# board_kelengkeng_v2.net
KiCad netlist of a schematic drawn in EAGLE
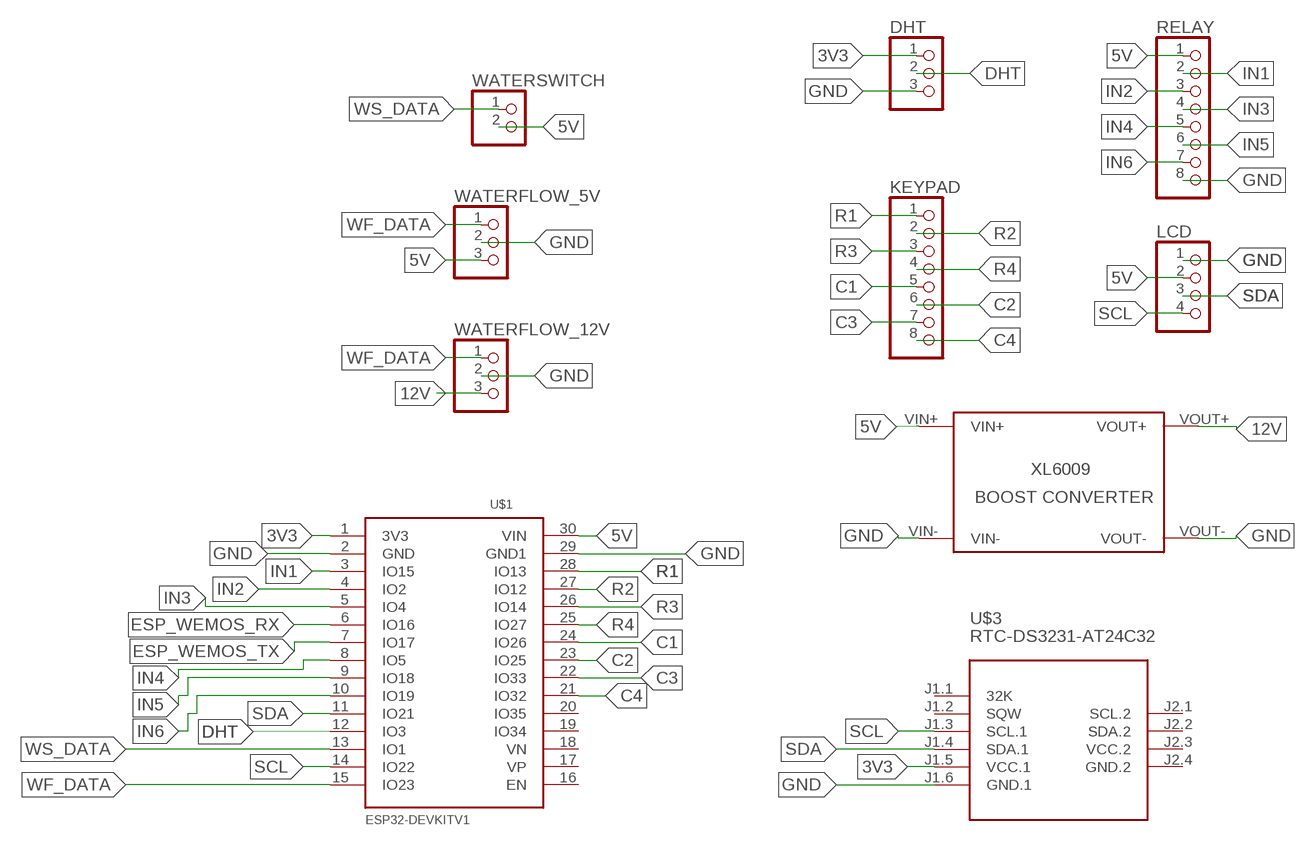
[diagram p0: schematic, sheet 1]

(export (version "E")
  (design (tool "Eeschema 10.0.6"))
  (components
    (comp (ref "DHT")
      (value "PINHD-1X3")
      (footprint "eagle-import:1X03")
      (libsource (lib "eagle-import") (part "PINHD-1X3"))
    )
    (comp (ref "KEYPAD")
      (value "PINHD-1X8")
      (footprint "eagle-import:1X08")
      (libsource (lib "eagle-import") (part "PINHD-1X8"))
    )
    (comp (ref "LCD")
      (value "PINHD-1X4")
      (footprint "eagle-import:1X04")
      (libsource (lib "eagle-import") (part "PINHD-1X4"))
    )
    (comp (ref "RELAY")
      (value "PINHD-1X8")
      (footprint "eagle-import:1X08")
      (libsource (lib "eagle-import") (part "PINHD-1X8"))
    )
    (comp (ref "U$1")
      (value "ESP32DEVKITV1")
      (footprint "eagle-import:ESP32-DEVKITV1")
      (libsource (lib "eagle-import") (part "ESP32DEVKITV1"))
    )
    (comp (ref "U$2")
      (value "XL6009")
      (footprint "eagle-import:XL6009")
      (libsource (lib "eagle-import") (part "XL6009"))
    )
    (comp (ref "U$3")
      (value "RTC-DS3231-AT24C32")
      (footprint "eagle-import:RTC-DS3231-AT24C32")
      (libsource (lib "eagle-import") (part "RTC-DS3231-AT24C32"))
    )
    (comp (ref "WATERFLOW_5V")
      (value "PINHD-1X3")
      (footprint "eagle-import:1X03")
      (libsource (lib "eagle-import") (part "PINHD-1X3"))
    )
    (comp (ref "WATERFLOW_12V")
      (value "PINHD-1X3")
      (footprint "eagle-import:1X03")
      (libsource (lib "eagle-import") (part "PINHD-1X3"))
    )
    (comp (ref "WATERSWITCH")
      (value "PINHD-1X2")
      (footprint "eagle-import:1X02")
      (libsource (lib "eagle-import") (part "PINHD-1X2"))
    )
  )
  (nets
    (net (code "1") (name "/GND.2") (class "Default")
      (node (ref "U$3") (pin "J2.4") (pinfunction "GND.2_J2.4") (pintype "power_in"))
    )
    (net (code "2") (name "/VCC.2") (class "Default")
      (node (ref "U$3") (pin "J2.3") (pinfunction "VCC.2_J2.3") (pintype "power_in"))
    )
    (net (code "3") (name "3V3") (class "Default")
      (node (ref "DHT") (pin "1") (pinfunction "1_1") (pintype "passive"))
      (node (ref "U$1") (pin "1") (pinfunction "3V3_1") (pintype "bidirectional"))
      (node (ref "U$3") (pin "J1.5") (pinfunction "VCC.1_J1.5") (pintype "power_in"))
    )
    (net (code "4") (name "5V") (class "Default")
      (node (ref "LCD") (pin "2") (pinfunction "2_2") (pintype "passive"))
      (node (ref "RELAY") (pin "1") (pinfunction "1_1") (pintype "passive"))
      (node (ref "U$1") (pin "30") (pinfunction "VIN_30") (pintype "bidirectional"))
      (node (ref "U$2") (pin "VIN+") (pinfunction "VIN+_VIN+") (pintype "bidirectional"))
      (node (ref "WATERFLOW_5V") (pin "3") (pinfunction "3_3") (pintype "passive"))
      (node (ref "WATERSWITCH") (pin "2") (pinfunction "2_2") (pintype "passive"))
    )
    (net (code "5") (name "12V") (class "Default")
      (node (ref "U$2") (pin "VOUT+") (pinfunction "VOUT+_VOUT+") (pintype "bidirectional"))
      (node (ref "WATERFLOW_12V") (pin "3") (pinfunction "3_3") (pintype "passive"))
    )
    (net (code "6") (name "C1") (class "Default")
      (node (ref "KEYPAD") (pin "5") (pinfunction "5_5") (pintype "passive"))
      (node (ref "U$1") (pin "24") (pinfunction "IO26_24") (pintype "bidirectional"))
    )
    (net (code "7") (name "C2") (class "Default")
      (node (ref "KEYPAD") (pin "6") (pinfunction "6_6") (pintype "passive"))
      (node (ref "U$1") (pin "23") (pinfunction "IO25_23") (pintype "bidirectional"))
    )
    (net (code "8") (name "C3") (class "Default")
      (node (ref "KEYPAD") (pin "7") (pinfunction "7_7") (pintype "passive"))
      (node (ref "U$1") (pin "22") (pinfunction "IO33_22") (pintype "bidirectional"))
    )
    (net (code "9") (name "C4") (class "Default")
      (node (ref "KEYPAD") (pin "8") (pinfunction "8_8") (pintype "passive"))
      (node (ref "U$1") (pin "21") (pinfunction "IO32_21") (pintype "bidirectional"))
    )
    (net (code "10") (name "DHT") (class "Default")
      (node (ref "DHT") (pin "2") (pinfunction "2_2") (pintype "passive"))
      (node (ref "U$1") (pin "12") (pinfunction "IO3_12") (pintype "bidirectional"))
    )
    (net (code "11") (name "ESP_WEMOS_RX") (class "Default")
      (node (ref "U$1") (pin "6") (pinfunction "IO16_6") (pintype "bidirectional"))
    )
    (net (code "12") (name "ESP_WEMOS_TX") (class "Default")
      (node (ref "U$1") (pin "7") (pinfunction "IO17_7") (pintype "bidirectional"))
    )
    (net (code "13") (name "GND") (class "Default")
      (node (ref "DHT") (pin "3") (pinfunction "3_3") (pintype "passive"))
      (node (ref "LCD") (pin "1") (pinfunction "1_1") (pintype "passive"))
      (node (ref "RELAY") (pin "8") (pinfunction "8_8") (pintype "passive"))
      (node (ref "U$1") (pin "2") (pinfunction "GND_2") (pintype "bidirectional"))
      (node (ref "U$1") (pin "29") (pinfunction "GND1_29") (pintype "bidirectional"))
      (node (ref "U$2") (pin "VIN-") (pinfunction "VIN-_VIN-") (pintype "bidirectional"))
      (node (ref "U$2") (pin "VOUT-") (pinfunction "VOUT-_VOUT-") (pintype "bidirectional"))
      (node (ref "U$3") (pin "J1.6") (pinfunction "GND.1_J1.6") (pintype "power_in"))
      (node (ref "WATERFLOW_12V") (pin "2") (pinfunction "2_2") (pintype "passive"))
      (node (ref "WATERFLOW_5V") (pin "2") (pinfunction "2_2") (pintype "passive"))
    )
    (net (code "14") (name "IN1") (class "Default")
      (node (ref "RELAY") (pin "2") (pinfunction "2_2") (pintype "passive"))
      (node (ref "U$1") (pin "3") (pinfunction "IO15_3") (pintype "bidirectional"))
    )
    (net (code "15") (name "IN2") (class "Default")
      (node (ref "RELAY") (pin "3") (pinfunction "3_3") (pintype "passive"))
      (node (ref "U$1") (pin "4") (pinfunction "IO2_4") (pintype "bidirectional"))
    )
    (net (code "16") (name "IN3") (class "Default")
      (node (ref "RELAY") (pin "4") (pinfunction "4_4") (pintype "passive"))
      (node (ref "U$1") (pin "5") (pinfunction "IO4_5") (pintype "bidirectional"))
    )
    (net (code "17") (name "IN4") (class "Default")
      (node (ref "RELAY") (pin "5") (pinfunction "5_5") (pintype "passive"))
      (node (ref "U$1") (pin "8") (pinfunction "IO5_8") (pintype "bidirectional"))
    )
    (net (code "18") (name "IN5") (class "Default")
      (node (ref "RELAY") (pin "6") (pinfunction "6_6") (pintype "passive"))
      (node (ref "U$1") (pin "9") (pinfunction "IO18_9") (pintype "bidirectional"))
    )
    (net (code "19") (name "IN6") (class "Default")
      (node (ref "RELAY") (pin "7") (pinfunction "7_7") (pintype "passive"))
      (node (ref "U$1") (pin "10") (pinfunction "IO19_10") (pintype "bidirectional"))
    )
    (net (code "20") (name "R1") (class "Default")
      (node (ref "KEYPAD") (pin "1") (pinfunction "1_1") (pintype "passive"))
      (node (ref "U$1") (pin "28") (pinfunction "IO13_28") (pintype "bidirectional"))
    )
    (net (code "21") (name "R2") (class "Default")
      (node (ref "KEYPAD") (pin "2") (pinfunction "2_2") (pintype "passive"))
      (node (ref "U$1") (pin "27") (pinfunction "IO12_27") (pintype "bidirectional"))
    )
    (net (code "22") (name "R3") (class "Default")
      (node (ref "KEYPAD") (pin "3") (pinfunction "3_3") (pintype "passive"))
      (node (ref "U$1") (pin "26") (pinfunction "IO14_26") (pintype "bidirectional"))
    )
    (net (code "23") (name "R4") (class "Default")
      (node (ref "KEYPAD") (pin "4") (pinfunction "4_4") (pintype "passive"))
      (node (ref "U$1") (pin "25") (pinfunction "IO27_25") (pintype "bidirectional"))
    )
    (net (code "24") (name "SCL") (class "Default")
      (node (ref "LCD") (pin "4") (pinfunction "4_4") (pintype "passive"))
      (node (ref "U$1") (pin "14") (pinfunction "IO22_14") (pintype "bidirectional"))
      (node (ref "U$3") (pin "J1.3") (pinfunction "SCL.1_J1.3") (pintype "bidirectional"))
    )
    (net (code "25") (name "SDA") (class "Default")
      (node (ref "LCD") (pin "3") (pinfunction "3_3") (pintype "passive"))
      (node (ref "U$1") (pin "11") (pinfunction "IO21_11") (pintype "bidirectional"))
      (node (ref "U$3") (pin "J1.4") (pinfunction "SDA.1_J1.4") (pintype "bidirectional"))
    )
    (net (code "26") (name "WF_DATA") (class "Default")
      (node (ref "U$1") (pin "15") (pinfunction "IO23_15") (pintype "bidirectional"))
      (node (ref "WATERFLOW_12V") (pin "1") (pinfunction "1_1") (pintype "passive"))
      (node (ref "WATERFLOW_5V") (pin "1") (pinfunction "1_1") (pintype "passive"))
    )
    (net (code "27") (name "WS_DATA") (class "Default")
      (node (ref "U$1") (pin "13") (pinfunction "IO1_13") (pintype "bidirectional"))
      (node (ref "WATERSWITCH") (pin "1") (pinfunction "1_1") (pintype "passive"))
    )
    (net (code "28") (name "unconnected-(U$1-EN-Pad16)") (class "Default")
      (node (ref "U$1") (pin "16") (pinfunction "EN_16") (pintype "bidirectional"))
    )
    (net (code "29") (name "unconnected-(U$1-IO34-Pad19)") (class "Default")
      (node (ref "U$1") (pin "19") (pinfunction "IO34_19") (pintype "bidirectional"))
    )
    (net (code "30") (name "unconnected-(U$1-IO35-Pad20)") (class "Default")
      (node (ref "U$1") (pin "20") (pinfunction "IO35_20") (pintype "bidirectional"))
    )
    (net (code "31") (name "unconnected-(U$1-VN-Pad18)") (class "Default")
      (node (ref "U$1") (pin "18") (pinfunction "VN_18") (pintype "bidirectional"))
    )
    (net (code "32") (name "unconnected-(U$1-VP-Pad17)") (class "Default")
      (node (ref "U$1") (pin "17") (pinfunction "VP_17") (pintype "bidirectional"))
    )
    (net (code "33") (name "unconnected-(U$3-32K-PadJ1.1)") (class "Default")
      (node (ref "U$3") (pin "J1.1") (pinfunction "32K_J1.1") (pintype "bidirectional"))
    )
    (net (code "34") (name "unconnected-(U$3-SCL.2-PadJ2.1)") (class "Default")
      (node (ref "U$3") (pin "J2.1") (pinfunction "SCL.2_J2.1") (pintype "bidirectional"))
    )
    (net (code "35") (name "unconnected-(U$3-SDA.2-PadJ2.2)") (class "Default")
      (node (ref "U$3") (pin "J2.2") (pinfunction "SDA.2_J2.2") (pintype "bidirectional"))
    )
    (net (code "36") (name "unconnected-(U$3-SQW-PadJ1.2)") (class "Default")
      (node (ref "U$3") (pin "J1.2") (pinfunction "SQW_J1.2") (pintype "bidirectional"))
    )
  )
)
